# 4-20mA.net
KiCad netlist of a schematic drawn in Altium Designer
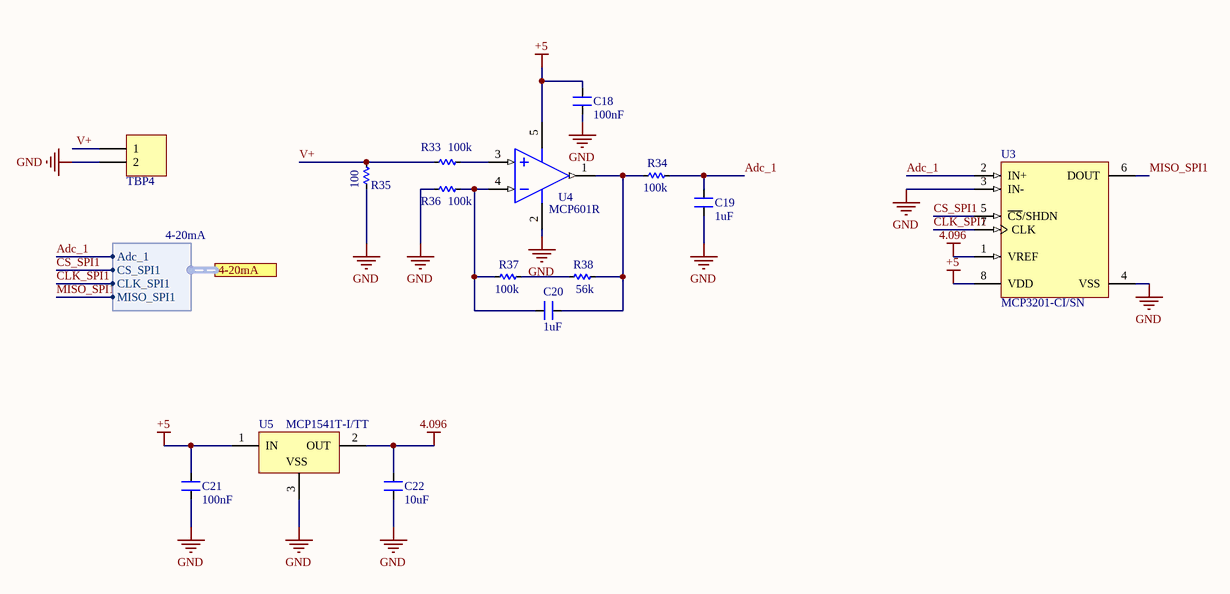
[diagram p0: 4-20mA.SchDoc]

(export (version "E")
  (design (tool "Eeschema 10.0.6"))
  (components
    (comp (ref "C18") (value "100nF") (footprint "CN-SMD-0603") (libsource (lib "thu vien 3d") (part "CN")))
    (comp (ref "C19") (value "1uF") (footprint "CN-SMD-0603") (libsource (lib "thu vien 3d") (part "CN")))
    (comp (ref "C20") (value "1uF") (footprint "CN-SMD-0603") (libsource (lib "thu vien 3d") (part "CN")))
    (comp (ref "C21") (value "100nF") (footprint "CN-SMD-0603") (libsource (lib "thu vien 3d") (part "CN")))
    (comp (ref "C22") (value "10uF") (footprint "CN-SMD-0805") (libsource (lib "thu vien 3d") (part "CN")))
    (comp (ref "R33")
      (value "100k")
      (footprint "RES-SMD-0603")
      (description "Resistor")
      (fields
        (field (name "MANUFACTURER") "Generic Components")
        (field (name "PUBLISHER") "Altium Hobart Technology Centre")
      )
      (libsource (lib "thu vien 3d") (part "Res-SMD"))
    )
    (comp (ref "R34")
      (value "100k")
      (footprint "RES-SMD-0603")
      (description "Resistor")
      (fields
        (field (name "MANUFACTURER") "Generic Components")
        (field (name "PUBLISHER") "Altium Hobart Technology Centre")
      )
      (libsource (lib "thu vien 3d") (part "Res-SMD"))
    )
    (comp (ref "R35")
      (value "100")
      (footprint "RES-SMD-0603")
      (description "Resistor")
      (fields
        (field (name "MANUFACTURER") "Generic Components")
        (field (name "PUBLISHER") "Altium Hobart Technology Centre")
      )
      (libsource (lib "thu vien 3d") (part "Res-SMD"))
    )
    (comp (ref "R36")
      (value "100k")
      (footprint "RES-SMD-0603")
      (description "Resistor")
      (fields
        (field (name "MANUFACTURER") "Generic Components")
        (field (name "PUBLISHER") "Altium Hobart Technology Centre")
      )
      (libsource (lib "thu vien 3d") (part "Res-SMD"))
    )
    (comp (ref "R37")
      (value "100k")
      (footprint "RES-SMD-0603")
      (description "Resistor")
      (fields
        (field (name "MANUFACTURER") "Generic Components")
        (field (name "PUBLISHER") "Altium Hobart Technology Centre")
      )
      (libsource (lib "thu vien 3d") (part "Res-SMD"))
    )
    (comp (ref "R38")
      (value "56k")
      (footprint "RES-SMD-0603")
      (description "Resistor")
      (fields
        (field (name "MANUFACTURER") "Generic Components")
        (field (name "PUBLISHER") "Altium Hobart Technology Centre")
      )
      (libsource (lib "thu vien 3d") (part "Res-SMD"))
    )
    (comp (ref "TBP4")
      (value "WE-Terminal Blocks Plugable Type 691322310002")
      (footprint "Terminal_Blocks_Pluggable_Socket__Right_Angle__3.81_mm_Pitch__2_Position")
      (description "WR-TBL Terminal block - serie 322 - 3.81 mm")
      (libsource (lib "All Library") (part "Terminal_Blocks_Pluggable_Socket__Right_Angle__3.81_mm_Pitch__2_Position"))
    )
    (comp (ref "U3")
      (value "MCP3201-CI/SN")
      (footprint "MCP3201")
      (libsource (lib "All Library") (part "MCP3201-CI/SN"))
    )
    (comp (ref "U4")
      (value "MCP601R")
      (footprint "MCP601")
      (fields (field (name "PARTNUMBER") "MCP601RT-I/OT"))
      (libsource (lib "Nichietsuvn") (part "MCP601RT-I/OT"))
    )
    (comp (ref "U5")
      (value "MCP1541T-I/TT")
      (footprint "MCP1541")
      (description "4.096V Voltage Reference, 3-Pin SOT-23, Industrial Temperature, Tape and Reel")
      (libsource (lib "All Library") (part "MCP1541T-I/TT"))
    )
  )
  (nets
    (net (code "2") (name "+5") (class "Default")
      (node (ref "C18") (pin "2") (pinfunction "2_2") (pintype "passive"))
      (node (ref "C21") (pin "1") (pinfunction "1_1") (pintype "passive"))
      (node (ref "U3") (pin "8") (pinfunction "VDD_8") (pintype "power_in"))
      (node (ref "U4") (pin "5") (pinfunction "VSS_5") (pintype "power_in"))
      (node (ref "U5") (pin "1") (pinfunction "IN_1") (pintype "power_in"))
    )
    (net (code "3") (name "/Adc_1") (class "Default")
      (node (ref "C19") (pin "1") (pinfunction "1_1") (pintype "passive"))
      (node (ref "R34") (pin "1") (pinfunction "1_1") (pintype "passive"))
      (node (ref "U3") (pin "2") (pinfunction "IN+_2") (pintype "input"))
    )
    (net (code "4") (name "/CLK_SPI1") (class "Default")
      (node (ref "U3") (pin "7") (pinfunction "CLK_7") (pintype "input"))
    )
    (net (code "5") (name "/CS_SPI1") (class "Default")
      (node (ref "U3") (pin "5") (pinfunction "~{CS}/SHDN_5") (pintype "input"))
    )
    (net (code "6") (name "/MISO_SPI1") (class "Default")
      (node (ref "U3") (pin "6") (pinfunction "DOUT_6") (pintype "tri_state"))
    )
    (net (code "7") (name "/V+") (class "Default")
      (node (ref "R33") (pin "2") (pinfunction "2_2") (pintype "passive"))
      (node (ref "R35") (pin "1") (pinfunction "1_1") (pintype "passive"))
      (node (ref "TBP4") (pin "1") (pinfunction "1_1") (pintype "passive"))
    )
    (net (code "9") (name "4.096") (class "Default")
      (node (ref "C22") (pin "1") (pinfunction "1_1") (pintype "passive"))
      (node (ref "U3") (pin "1") (pinfunction "VREF_1") (pintype "input"))
      (node (ref "U5") (pin "2") (pinfunction "OUT_2") (pintype "power_in"))
    )
    (net (code "10") (name "GND") (class "Default")
      (node (ref "C18") (pin "1") (pinfunction "1_1") (pintype "passive"))
      (node (ref "C19") (pin "2") (pinfunction "2_2") (pintype "passive"))
      (node (ref "C21") (pin "2") (pinfunction "2_2") (pintype "passive"))
      (node (ref "C22") (pin "2") (pinfunction "2_2") (pintype "passive"))
      (node (ref "R35") (pin "2") (pinfunction "2_2") (pintype "passive"))
      (node (ref "R36") (pin "2") (pinfunction "2_2") (pintype "passive"))
      (node (ref "TBP4") (pin "2") (pinfunction "2_2") (pintype "passive"))
      (node (ref "U3") (pin "3") (pinfunction "IN-_3") (pintype "input"))
      (node (ref "U3") (pin "4") (pinfunction "VSS_4") (pintype "power_in"))
      (node (ref "U4") (pin "2") (pinfunction "VDD_2") (pintype "power_in"))
      (node (ref "U5") (pin "3") (pinfunction "VSS_3") (pintype "power_in"))
    )
    (net (code "11") (name "Net-(R37-Pad1)") (class "Default")
      (node (ref "R37") (pin "1") (pinfunction "1_1") (pintype "passive"))
      (node (ref "R38") (pin "2") (pinfunction "2_2") (pintype "passive"))
    )
    (net (code "12") (name "Net-(U4-VIN+)") (class "Default")
      (node (ref "R33") (pin "1") (pinfunction "1_1") (pintype "passive"))
      (node (ref "U4") (pin "3") (pinfunction "VIN+_3") (pintype "input"))
    )
    (net (code "13") (name "Net-(U4-VIN-)") (class "Default")
      (node (ref "C20") (pin "2") (pinfunction "2_2") (pintype "passive"))
      (node (ref "R36") (pin "1") (pinfunction "1_1") (pintype "passive"))
      (node (ref "R37") (pin "2") (pinfunction "2_2") (pintype "passive"))
      (node (ref "U4") (pin "4") (pinfunction "VIN-_4") (pintype "input"))
    )
    (net (code "14") (name "Net-(U4-VOUT)") (class "Default")
      (node (ref "C20") (pin "1") (pinfunction "1_1") (pintype "passive"))
      (node (ref "R34") (pin "2") (pinfunction "2_2") (pintype "passive"))
      (node (ref "R38") (pin "1") (pinfunction "1_1") (pintype "passive"))
      (node (ref "U4") (pin "1") (pinfunction "VOUT_1") (pintype "output"))
    )
  )
)
